# interface_board_circuit.net
KiCad netlist of a schematic drawn in EAGLE
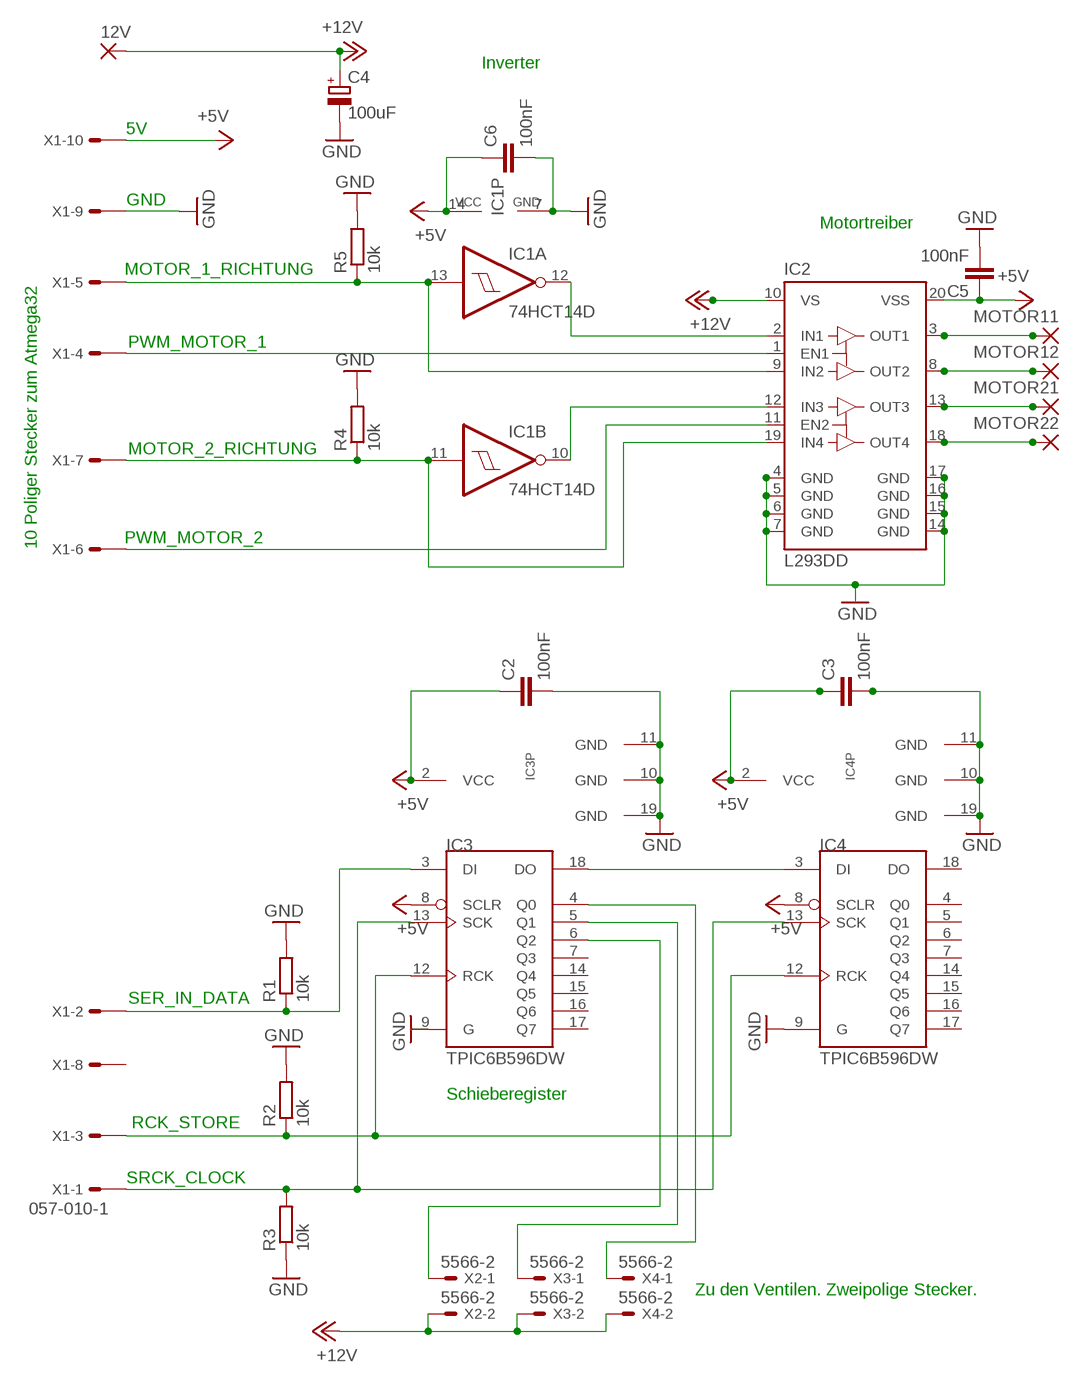
[diagram p0: schematic, sheet 1]

(export (version "E")
  (design (tool "Eeschema 10.0.6"))
  (components
    (comp (ref "12V")
      (value "1,6/0,9")
      (footprint "eagle-import:1,6_0,9")
      (libsource (lib "eagle-import") (part "1,6/0,9"))
    )
    (comp (ref "C2")
      (value "100nF")
      (footprint "eagle-import:C0603")
      (libsource (lib "eagle-import") (part "C-EUC0603"))
    )
    (comp (ref "C3")
      (value "100nF")
      (footprint "eagle-import:C0603")
      (libsource (lib "eagle-import") (part "C-EUC0603"))
    )
    (comp (ref "C4")
      (value "100uF")
      (footprint "eagle-import:PANASONIC_D")
      (libsource (lib "eagle-import") (part "CPOL-EUD"))
    )
    (comp (ref "C5")
      (value "100nF")
      (footprint "eagle-import:C0603")
      (libsource (lib "eagle-import") (part "C-EUC0603"))
    )
    (comp (ref "C6")
      (value "100nF")
      (footprint "eagle-import:C0603")
      (libsource (lib "eagle-import") (part "C-EUC0603"))
    )
    (comp (ref "IC1")
      (value "74HCT14D")
      (footprint "eagle-import:SO14")
      (libsource (lib "eagle-import") (part "7414DHCT"))
    )
    (comp (ref "IC2")
      (value "L293DD")
      (footprint "eagle-import:SO20")
      (libsource (lib "eagle-import") (part "L293DD"))
    )
    (comp (ref "IC3")
      (value "TPIC6B596DW")
      (footprint "eagle-import:SO20W")
      (libsource (lib "eagle-import") (part "TPIC6B596DW"))
    )
    (comp (ref "IC4")
      (value "TPIC6B596DW")
      (footprint "eagle-import:SO20W")
      (libsource (lib "eagle-import") (part "TPIC6B596DW"))
    )
    (comp (ref "MOTOR11")
      (value "2,54/1,1")
      (footprint "eagle-import:2,54_1,1")
      (libsource (lib "eagle-import") (part "2,54/1,1"))
    )
    (comp (ref "MOTOR12")
      (value "2,54/1,1")
      (footprint "eagle-import:2,54_1,1")
      (libsource (lib "eagle-import") (part "2,54/1,1"))
    )
    (comp (ref "MOTOR21")
      (value "2,54/1,1")
      (footprint "eagle-import:2,54_1,1")
      (libsource (lib "eagle-import") (part "2,54/1,1"))
    )
    (comp (ref "MOTOR22")
      (value "2,54/1,1")
      (footprint "eagle-import:2,54_1,1")
      (libsource (lib "eagle-import") (part "2,54/1,1"))
    )
    (comp (ref "R1")
      (value "10k")
      (footprint "eagle-import:M0805")
      (libsource (lib "eagle-import") (part "R-EU_M0805"))
    )
    (comp (ref "R2")
      (value "10k")
      (footprint "eagle-import:M0805")
      (libsource (lib "eagle-import") (part "R-EU_M0805"))
    )
    (comp (ref "R3")
      (value "10k")
      (footprint "eagle-import:M0805")
      (libsource (lib "eagle-import") (part "R-EU_M0805"))
    )
    (comp (ref "R4")
      (value "10k")
      (footprint "eagle-import:M0805")
      (libsource (lib "eagle-import") (part "R-EU_M0805"))
    )
    (comp (ref "R5")
      (value "10k")
      (footprint "eagle-import:M0805")
      (libsource (lib "eagle-import") (part "R-EU_M0805"))
    )
    (comp (ref "X1")
      (value "057-010-1")
      (footprint "eagle-import:057-010-1")
      (libsource (lib "eagle-import") (part "057-010-1"))
    )
    (comp (ref "X2")
      (value "5566-2")
      (footprint "eagle-import:5566-2")
      (libsource (lib "eagle-import") (part "5566-2"))
    )
    (comp (ref "X3")
      (value "5566-2")
      (footprint "eagle-import:5566-2")
      (libsource (lib "eagle-import") (part "5566-2"))
    )
    (comp (ref "X4")
      (value "5566-2")
      (footprint "eagle-import:5566-2")
      (libsource (lib "eagle-import") (part "5566-2"))
    )
  )
  (nets
    (net (code "1") (name "+5V") (class "Default")
      (node (ref "C2") (pin "1") (pinfunction "1_1") (pintype "passive"))
      (node (ref "C3") (pin "1") (pinfunction "1_1") (pintype "passive"))
      (node (ref "C5") (pin "1") (pinfunction "1_1") (pintype "passive"))
      (node (ref "C6") (pin "1") (pinfunction "1_1") (pintype "passive"))
      (node (ref "IC1") (pin "14") (pinfunction "VCC_14") (pintype "power_in"))
      (node (ref "IC2") (pin "20") (pinfunction "VSS_20") (pintype "power_in"))
      (node (ref "IC3") (pin "2") (pinfunction "VCC_2") (pintype "power_in"))
      (node (ref "IC3") (pin "8") (pinfunction "SCLR_8") (pintype "input"))
      (node (ref "IC4") (pin "2") (pinfunction "VCC_2") (pintype "power_in"))
      (node (ref "IC4") (pin "8") (pinfunction "SCLR_8") (pintype "input"))
      (node (ref "X1") (pin "10") (pinfunction "S_10") (pintype "passive"))
    )
    (net (code "2") (name "+12V") (class "Default")
      (node (ref "12V") (pin "1") (pinfunction "P_1") (pintype "passive"))
      (node (ref "C4") (pin "+") (pinfunction "+_+") (pintype "passive"))
      (node (ref "IC2") (pin "10") (pinfunction "VS_10") (pintype "power_in"))
      (node (ref "X2") (pin "2") (pinfunction "S_2") (pintype "passive"))
      (node (ref "X3") (pin "2") (pinfunction "S_2") (pintype "passive"))
      (node (ref "X4") (pin "2") (pinfunction "S_2") (pintype "passive"))
    )
    (net (code "3") (name "GND") (class "Default")
      (node (ref "C2") (pin "2") (pinfunction "2_2") (pintype "passive"))
      (node (ref "C3") (pin "2") (pinfunction "2_2") (pintype "passive"))
      (node (ref "C4") (pin "-") (pinfunction "-_-") (pintype "passive"))
      (node (ref "C5") (pin "2") (pinfunction "2_2") (pintype "passive"))
      (node (ref "C6") (pin "2") (pinfunction "2_2") (pintype "passive"))
      (node (ref "IC1") (pin "7") (pinfunction "GND_7") (pintype "power_in"))
      (node (ref "IC2") (pin "14") (pinfunction "GND_14") (pintype "power_in"))
      (node (ref "IC2") (pin "15") (pinfunction "GND_15") (pintype "power_in"))
      (node (ref "IC2") (pin "16") (pinfunction "GND_16") (pintype "power_in"))
      (node (ref "IC2") (pin "17") (pinfunction "GND_17") (pintype "power_in"))
      (node (ref "IC2") (pin "4") (pinfunction "GND_4") (pintype "power_in"))
      (node (ref "IC2") (pin "5") (pinfunction "GND_5") (pintype "power_in"))
      (node (ref "IC2") (pin "6") (pinfunction "GND_6") (pintype "power_in"))
      (node (ref "IC2") (pin "7") (pinfunction "GND_7") (pintype "power_in"))
      (node (ref "IC3") (pin "10") (pinfunction "GND_10") (pintype "power_in"))
      (node (ref "IC3") (pin "11") (pinfunction "GND_11") (pintype "power_in"))
      (node (ref "IC3") (pin "19") (pinfunction "GND_19") (pintype "power_in"))
      (node (ref "IC3") (pin "9") (pinfunction "G_9") (pintype "input"))
      (node (ref "IC4") (pin "10") (pinfunction "GND_10") (pintype "power_in"))
      (node (ref "IC4") (pin "11") (pinfunction "GND_11") (pintype "power_in"))
      (node (ref "IC4") (pin "19") (pinfunction "GND_19") (pintype "power_in"))
      (node (ref "IC4") (pin "9") (pinfunction "G_9") (pintype "input"))
      (node (ref "R1") (pin "2") (pinfunction "2_2") (pintype "passive"))
      (node (ref "R2") (pin "2") (pinfunction "2_2") (pintype "passive"))
      (node (ref "R3") (pin "1") (pinfunction "1_1") (pintype "passive"))
      (node (ref "R4") (pin "2") (pinfunction "2_2") (pintype "passive"))
      (node (ref "R5") (pin "2") (pinfunction "2_2") (pintype "passive"))
      (node (ref "X1") (pin "9") (pinfunction "S_9") (pintype "passive"))
    )
    (net (code "4") (name "Net-(IC1A-I)") (class "Default")
      (node (ref "IC1") (pin "13") (pinfunction "I_13") (pintype "input"))
      (node (ref "IC2") (pin "9") (pinfunction "IN2_9") (pintype "input"))
      (node (ref "R5") (pin "1") (pinfunction "1_1") (pintype "passive"))
      (node (ref "X1") (pin "5") (pinfunction "S_5") (pintype "passive"))
    )
    (net (code "5") (name "Net-(IC1A-O)") (class "Default")
      (node (ref "IC1") (pin "12") (pinfunction "O_12") (pintype "output"))
      (node (ref "IC2") (pin "2") (pinfunction "IN1_2") (pintype "input"))
    )
    (net (code "6") (name "Net-(IC1B-I)") (class "Default")
      (node (ref "IC1") (pin "11") (pinfunction "I_11") (pintype "input"))
      (node (ref "IC2") (pin "19") (pinfunction "IN4_19") (pintype "input"))
      (node (ref "R4") (pin "1") (pinfunction "1_1") (pintype "passive"))
      (node (ref "X1") (pin "7") (pinfunction "S_7") (pintype "passive"))
    )
    (net (code "7") (name "Net-(IC1B-O)") (class "Default")
      (node (ref "IC1") (pin "10") (pinfunction "O_10") (pintype "output"))
      (node (ref "IC2") (pin "12") (pinfunction "IN3_12") (pintype "input"))
    )
    (net (code "8") (name "Net-(IC2-EN1)") (class "Default")
      (node (ref "IC2") (pin "1") (pinfunction "EN1_1") (pintype "input"))
      (node (ref "X1") (pin "4") (pinfunction "S_4") (pintype "passive"))
    )
    (net (code "9") (name "Net-(IC2-EN2)") (class "Default")
      (node (ref "IC2") (pin "11") (pinfunction "EN2_11") (pintype "input"))
      (node (ref "X1") (pin "6") (pinfunction "S_6") (pintype "passive"))
    )
    (net (code "10") (name "Net-(IC2-OUT1)") (class "Default")
      (node (ref "IC2") (pin "3") (pinfunction "OUT1_3") (pintype "output"))
      (node (ref "MOTOR11") (pin "1") (pinfunction "P_1") (pintype "passive"))
    )
    (net (code "11") (name "Net-(IC2-OUT2)") (class "Default")
      (node (ref "IC2") (pin "8") (pinfunction "OUT2_8") (pintype "output"))
      (node (ref "MOTOR12") (pin "1") (pinfunction "P_1") (pintype "passive"))
    )
    (net (code "12") (name "Net-(IC2-OUT3)") (class "Default")
      (node (ref "IC2") (pin "13") (pinfunction "OUT3_13") (pintype "output"))
      (node (ref "MOTOR21") (pin "1") (pinfunction "P_1") (pintype "passive"))
    )
    (net (code "13") (name "Net-(IC2-OUT4)") (class "Default")
      (node (ref "IC2") (pin "18") (pinfunction "OUT4_18") (pintype "output"))
      (node (ref "MOTOR22") (pin "1") (pinfunction "P_1") (pintype "passive"))
    )
    (net (code "14") (name "Net-(IC3A-DI)") (class "Default")
      (node (ref "IC3") (pin "3") (pinfunction "DI_3") (pintype "input"))
      (node (ref "R1") (pin "1") (pinfunction "1_1") (pintype "passive"))
      (node (ref "X1") (pin "2") (pinfunction "S_2") (pintype "passive"))
    )
    (net (code "15") (name "Net-(IC3A-DO)") (class "Default")
      (node (ref "IC3") (pin "18") (pinfunction "DO_18") (pintype "output"))
      (node (ref "IC4") (pin "3") (pinfunction "DI_3") (pintype "input"))
    )
    (net (code "16") (name "Net-(IC3A-Q0)") (class "Default")
      (node (ref "IC3") (pin "4") (pinfunction "Q0_4") (pintype "open_collector"))
      (node (ref "X4") (pin "1") (pinfunction "S_1") (pintype "passive"))
    )
    (net (code "17") (name "Net-(IC3A-Q1)") (class "Default")
      (node (ref "IC3") (pin "5") (pinfunction "Q1_5") (pintype "open_collector"))
      (node (ref "X3") (pin "1") (pinfunction "S_1") (pintype "passive"))
    )
    (net (code "18") (name "Net-(IC3A-Q2)") (class "Default")
      (node (ref "IC3") (pin "6") (pinfunction "Q2_6") (pintype "open_collector"))
      (node (ref "X2") (pin "1") (pinfunction "S_1") (pintype "passive"))
    )
    (net (code "19") (name "Net-(IC3A-RCK)") (class "Default")
      (node (ref "IC3") (pin "12") (pinfunction "RCK_12") (pintype "input"))
      (node (ref "IC4") (pin "12") (pinfunction "RCK_12") (pintype "input"))
      (node (ref "R2") (pin "1") (pinfunction "1_1") (pintype "passive"))
      (node (ref "X1") (pin "3") (pinfunction "S_3") (pintype "passive"))
    )
    (net (code "20") (name "Net-(IC3A-SCK)") (class "Default")
      (node (ref "IC3") (pin "13") (pinfunction "SCK_13") (pintype "input"))
      (node (ref "IC4") (pin "13") (pinfunction "SCK_13") (pintype "input"))
      (node (ref "R3") (pin "2") (pinfunction "2_2") (pintype "passive"))
      (node (ref "X1") (pin "1") (pinfunction "S_1") (pintype "passive"))
    )
    (net (code "21") (name "unconnected-(IC3A-Q3-Pad7)") (class "Default")
      (node (ref "IC3") (pin "7") (pinfunction "Q3_7") (pintype "open_collector"))
    )
    (net (code "22") (name "unconnected-(IC3A-Q4-Pad14)") (class "Default")
      (node (ref "IC3") (pin "14") (pinfunction "Q4_14") (pintype "open_collector"))
    )
    (net (code "23") (name "unconnected-(IC3A-Q5-Pad15)") (class "Default")
      (node (ref "IC3") (pin "15") (pinfunction "Q5_15") (pintype "open_collector"))
    )
    (net (code "24") (name "unconnected-(IC3A-Q6-Pad16)") (class "Default")
      (node (ref "IC3") (pin "16") (pinfunction "Q6_16") (pintype "open_collector"))
    )
    (net (code "25") (name "unconnected-(IC3A-Q7-Pad17)") (class "Default")
      (node (ref "IC3") (pin "17") (pinfunction "Q7_17") (pintype "open_collector"))
    )
    (net (code "26") (name "unconnected-(IC4A-DO-Pad18)") (class "Default")
      (node (ref "IC4") (pin "18") (pinfunction "DO_18") (pintype "output"))
    )
    (net (code "27") (name "unconnected-(IC4A-Q0-Pad4)") (class "Default")
      (node (ref "IC4") (pin "4") (pinfunction "Q0_4") (pintype "open_collector"))
    )
    (net (code "28") (name "unconnected-(IC4A-Q1-Pad5)") (class "Default")
      (node (ref "IC4") (pin "5") (pinfunction "Q1_5") (pintype "open_collector"))
    )
    (net (code "29") (name "unconnected-(IC4A-Q2-Pad6)") (class "Default")
      (node (ref "IC4") (pin "6") (pinfunction "Q2_6") (pintype "open_collector"))
    )
    (net (code "30") (name "unconnected-(IC4A-Q3-Pad7)") (class "Default")
      (node (ref "IC4") (pin "7") (pinfunction "Q3_7") (pintype "open_collector"))
    )
    (net (code "31") (name "unconnected-(IC4A-Q4-Pad14)") (class "Default")
      (node (ref "IC4") (pin "14") (pinfunction "Q4_14") (pintype "open_collector"))
    )
    (net (code "32") (name "unconnected-(IC4A-Q5-Pad15)") (class "Default")
      (node (ref "IC4") (pin "15") (pinfunction "Q5_15") (pintype "open_collector"))
    )
    (net (code "33") (name "unconnected-(IC4A-Q6-Pad16)") (class "Default")
      (node (ref "IC4") (pin "16") (pinfunction "Q6_16") (pintype "open_collector"))
    )
    (net (code "34") (name "unconnected-(IC4A-Q7-Pad17)") (class "Default")
      (node (ref "IC4") (pin "17") (pinfunction "Q7_17") (pintype "open_collector"))
    )
    (net (code "35") (name "unconnected-(X1I-S-Pad8)") (class "Default")
      (node (ref "X1") (pin "8") (pinfunction "S_8") (pintype "passive"))
    )
  )
)
